# untitled.net
KiCad netlist of a schematic drawn in EAGLE
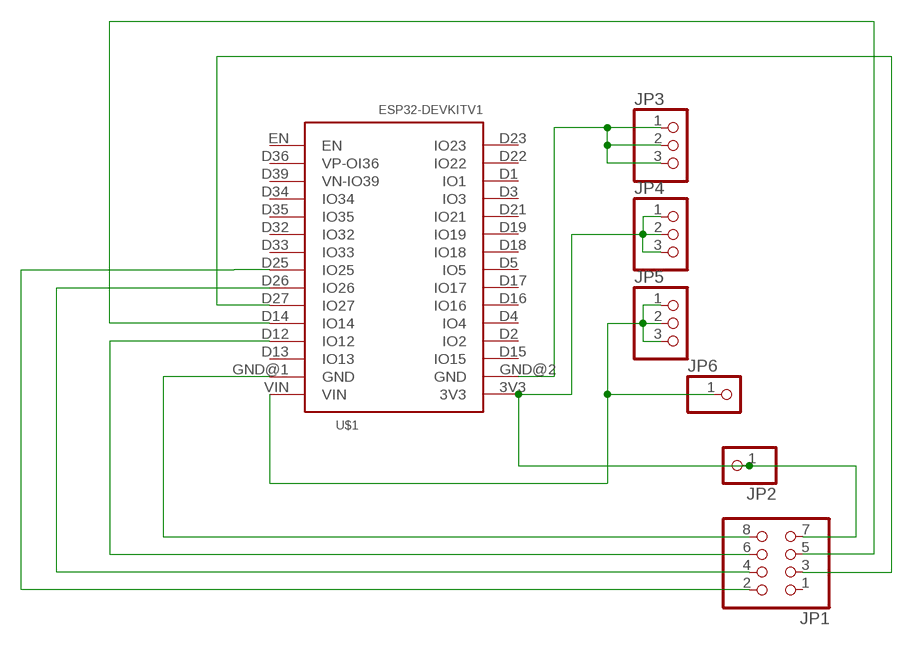
[diagram p0: schematic, sheet 1]

(export (version "E")
  (design (tool "Eeschema 10.0.6"))
  (components
    (comp (ref "JP1")
      (value "PINHD-2X4")
      (footprint "eagle-import:2X04")
      (libsource (lib "eagle-import") (part "PINHD-2X4"))
    )
    (comp (ref "JP2")
      (value "PINHD-1X1")
      (footprint "eagle-import:1X01")
      (libsource (lib "eagle-import") (part "PINHD-1X1"))
    )
    (comp (ref "JP3")
      (value "PINHD-1X3")
      (footprint "eagle-import:1X03")
      (libsource (lib "eagle-import") (part "PINHD-1X3"))
    )
    (comp (ref "JP4")
      (value "PINHD-1X3")
      (footprint "eagle-import:1X03")
      (libsource (lib "eagle-import") (part "PINHD-1X3"))
    )
    (comp (ref "JP5")
      (value "PINHD-1X3")
      (footprint "eagle-import:1X03")
      (libsource (lib "eagle-import") (part "PINHD-1X3"))
    )
    (comp (ref "JP6")
      (value "PINHD-1X1")
      (footprint "eagle-import:1X01")
      (libsource (lib "eagle-import") (part "PINHD-1X1"))
    )
    (comp (ref "U$1")
      (value "ESP32DEVKITV1")
      (footprint "eagle-import:ESP32-DEVKITV1")
      (libsource (lib "eagle-import") (part "ESP32DEVKITV1"))
    )
  )
  (nets
    (net (code "1") (name "Net-(JP1-Pad7)") (class "Default")
      (node (ref "JP1") (pin "7") (pinfunction "7_7") (pintype "passive"))
      (node (ref "JP2") (pin "1") (pinfunction "1_1") (pintype "passive"))
      (node (ref "JP4") (pin "1") (pinfunction "1_1") (pintype "passive"))
      (node (ref "JP4") (pin "2") (pinfunction "2_2") (pintype "passive"))
      (node (ref "JP4") (pin "3") (pinfunction "3_3") (pintype "passive"))
      (node (ref "U$1") (pin "3V3") (pinfunction "3V3_3V3") (pintype "bidirectional"))
    )
    (net (code "2") (name "Net-(JP1-Pad8)") (class "Default")
      (node (ref "JP1") (pin "8") (pinfunction "8_8") (pintype "passive"))
      (node (ref "U$1") (pin "GND@1") (pinfunction "GND_GND@1") (pintype "bidirectional"))
    )
    (net (code "3") (name "Net-(JP3-Pad1)") (class "Default")
      (node (ref "JP3") (pin "1") (pinfunction "1_1") (pintype "passive"))
      (node (ref "JP3") (pin "2") (pinfunction "2_2") (pintype "passive"))
      (node (ref "JP3") (pin "3") (pinfunction "3_3") (pintype "passive"))
      (node (ref "U$1") (pin "GND@2") (pinfunction "GND_GND@2") (pintype "bidirectional"))
    )
    (net (code "4") (name "Net-(JP5-Pad1)") (class "Default")
      (node (ref "JP5") (pin "1") (pinfunction "1_1") (pintype "passive"))
      (node (ref "JP5") (pin "2") (pinfunction "2_2") (pintype "passive"))
      (node (ref "JP5") (pin "3") (pinfunction "3_3") (pintype "passive"))
      (node (ref "JP6") (pin "1") (pinfunction "1_1") (pintype "passive"))
      (node (ref "U$1") (pin "VIN") (pinfunction "VIN_VIN") (pintype "bidirectional"))
    )
    (net (code "5") (name "Net-(U$1-IO12)") (class "Default")
      (node (ref "JP1") (pin "6") (pinfunction "6_6") (pintype "passive"))
      (node (ref "U$1") (pin "D12") (pinfunction "IO12_D12") (pintype "bidirectional"))
    )
    (net (code "6") (name "Net-(U$1-IO14)") (class "Default")
      (node (ref "JP1") (pin "5") (pinfunction "5_5") (pintype "passive"))
      (node (ref "U$1") (pin "D14") (pinfunction "IO14_D14") (pintype "bidirectional"))
    )
    (net (code "7") (name "Net-(U$1-IO25)") (class "Default")
      (node (ref "JP1") (pin "2") (pinfunction "2_2") (pintype "passive"))
      (node (ref "U$1") (pin "D25") (pinfunction "IO25_D25") (pintype "bidirectional"))
    )
    (net (code "8") (name "Net-(U$1-IO26)") (class "Default")
      (node (ref "JP1") (pin "4") (pinfunction "4_4") (pintype "passive"))
      (node (ref "U$1") (pin "D26") (pinfunction "IO26_D26") (pintype "bidirectional"))
    )
    (net (code "9") (name "Net-(U$1-IO27)") (class "Default")
      (node (ref "JP1") (pin "3") (pinfunction "3_3") (pintype "passive"))
      (node (ref "U$1") (pin "D27") (pinfunction "IO27_D27") (pintype "bidirectional"))
    )
    (net (code "10") (name "unconnected-(JP1-Pad1)") (class "Default")
      (node (ref "JP1") (pin "1") (pinfunction "1_1") (pintype "passive"))
    )
    (net (code "11") (name "unconnected-(U$1-IO1-PadD1)") (class "Default")
      (node (ref "U$1") (pin "D1") (pinfunction "IO1_D1") (pintype "bidirectional"))
    )
    (net (code "12") (name "unconnected-(U$1-IO2-PadD2)") (class "Default")
      (node (ref "U$1") (pin "D2") (pinfunction "IO2_D2") (pintype "bidirectional"))
    )
    (net (code "13") (name "unconnected-(U$1-IO3-PadD3)") (class "Default")
      (node (ref "U$1") (pin "D3") (pinfunction "IO3_D3") (pintype "bidirectional"))
    )
    (net (code "14") (name "unconnected-(U$1-IO4-PadD4)") (class "Default")
      (node (ref "U$1") (pin "D4") (pinfunction "IO4_D4") (pintype "bidirectional"))
    )
    (net (code "15") (name "unconnected-(U$1-IO5-PadD5)") (class "Default")
      (node (ref "U$1") (pin "D5") (pinfunction "IO5_D5") (pintype "bidirectional"))
    )
    (net (code "16") (name "unconnected-(U$1-IO13-PadD13)") (class "Default")
      (node (ref "U$1") (pin "D13") (pinfunction "IO13_D13") (pintype "bidirectional"))
    )
    (net (code "17") (name "unconnected-(U$1-IO15-PadD15)") (class "Default")
      (node (ref "U$1") (pin "D15") (pinfunction "IO15_D15") (pintype "bidirectional"))
    )
    (net (code "18") (name "unconnected-(U$1-IO16-PadD16)") (class "Default")
      (node (ref "U$1") (pin "D16") (pinfunction "IO16_D16") (pintype "bidirectional"))
    )
    (net (code "19") (name "unconnected-(U$1-IO17-PadD17)") (class "Default")
      (node (ref "U$1") (pin "D17") (pinfunction "IO17_D17") (pintype "bidirectional"))
    )
    (net (code "20") (name "unconnected-(U$1-IO18-PadD18)") (class "Default")
      (node (ref "U$1") (pin "D18") (pinfunction "IO18_D18") (pintype "bidirectional"))
    )
    (net (code "21") (name "unconnected-(U$1-IO19-PadD19)") (class "Default")
      (node (ref "U$1") (pin "D19") (pinfunction "IO19_D19") (pintype "bidirectional"))
    )
    (net (code "22") (name "unconnected-(U$1-IO21-PadD21)") (class "Default")
      (node (ref "U$1") (pin "D21") (pinfunction "IO21_D21") (pintype "bidirectional"))
    )
    (net (code "23") (name "unconnected-(U$1-IO22-PadD22)") (class "Default")
      (node (ref "U$1") (pin "D22") (pinfunction "IO22_D22") (pintype "bidirectional"))
    )
    (net (code "24") (name "unconnected-(U$1-IO23-PadD23)") (class "Default")
      (node (ref "U$1") (pin "D23") (pinfunction "IO23_D23") (pintype "bidirectional"))
    )
    (net (code "25") (name "unconnected-(U$1-IO32-PadD32)") (class "Default")
      (node (ref "U$1") (pin "D32") (pinfunction "IO32_D32") (pintype "bidirectional"))
    )
    (net (code "26") (name "unconnected-(U$1-IO33-PadD33)") (class "Default")
      (node (ref "U$1") (pin "D33") (pinfunction "IO33_D33") (pintype "bidirectional"))
    )
    (net (code "27") (name "unconnected-(U$1-IO34-PadD34)") (class "Default")
      (node (ref "U$1") (pin "D34") (pinfunction "IO34_D34") (pintype "bidirectional"))
    )
    (net (code "28") (name "unconnected-(U$1-IO35-PadD35)") (class "Default")
      (node (ref "U$1") (pin "D35") (pinfunction "IO35_D35") (pintype "bidirectional"))
    )
    (net (code "29") (name "unconnected-(U$1-PadEN)") (class "Default")
      (node (ref "U$1") (pin "EN") (pinfunction "EN_EN") (pintype "bidirectional"))
    )
    (net (code "30") (name "unconnected-(U$1-VN-IO39-PadD39)") (class "Default")
      (node (ref "U$1") (pin "D39") (pinfunction "VN-IO39_D39") (pintype "bidirectional"))
    )
    (net (code "31") (name "unconnected-(U$1-VP-OI36-PadD36)") (class "Default")
      (node (ref "U$1") (pin "D36") (pinfunction "VP-OI36_D36") (pintype "bidirectional"))
    )
  )
)
